# Isolation.net
KiCad netlist of a schematic drawn in Altium Designer
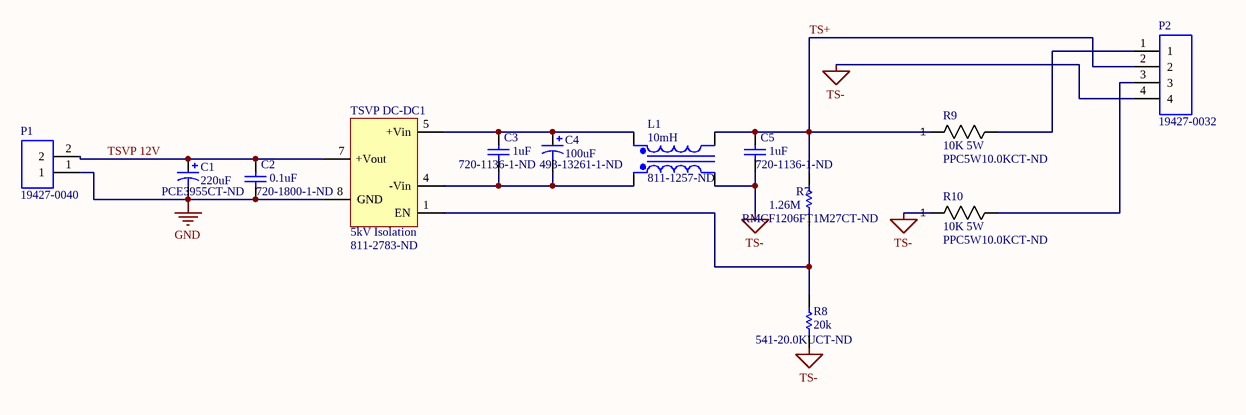
[diagram p0: Isolation.SchDoc]

(export (version "E")
  (design (tool "Eeschema 10.0.6"))
  (components
    (comp (ref "C1")
      (value "220uF")
      (footprint "EEE-1VA221UP")
      (description "Panasonic Electrolytic 35V, 20% EEE-1VA221UP")
      (fields (field (name "SUPPLIER PART NUMBER 1") "PCE3955CT-ND"))
      (libsource (lib "Isolation") (part "Cap Pol1"))
    )
    (comp (ref "C2")
      (value "0.1uF")
      (footprint "C1206")
      (description "C0603C104K3RACTU")
      (fields
        (field (name "SUPPLIER PART NUMBER 1") "720-1800-1-ND")
        (field (name "Comment") "C0603")
        (field (name "PUBLISHER") "Altium Limited")
      )
      (libsource (lib "Isolation") (part "C0603"))
    )
    (comp (ref "C3")
      (value "1uF")
      (footprint "2225 Package")
      (description "C0603C104K3RACTU")
      (fields
        (field (name "SUPPLIER PART NUMBER 1") "720-1136-1-ND")
        (field (name "Comment") "C0603")
        (field (name "PUBLISHER") "Altium Limited")
      )
      (libsource (lib "Isolation") (part "C0603_1"))
    )
    (comp (ref "C4")
      (value "100uF")
      (footprint "NichiconCAP")
      (description "Nichicon 200V 100uF TH Capacitor  UCA2D101MHD6TN")
      (fields (field (name "SUPPLIER PART NUMBER 1") "493-13261-1-ND"))
      (libsource (lib "Isolation") (part "Cap Pol1_1"))
    )
    (comp (ref "C5")
      (value "1uF")
      (footprint "2225 Package")
      (description "C0603C104K3RACTU")
      (fields
        (field (name "SUPPLIER PART NUMBER 1") "720-1136-1-ND")
        (field (name "Comment") "C0603")
        (field (name "PUBLISHER") "Altium Limited")
      )
      (libsource (lib "Isolation") (part "C0603_1"))
    )
    (comp (ref "L1")
      (value "10mH")
      (footprint "52106C")
      (description "MuRata 52106C Common Choke")
      (fields
        (field (name "SUPPLIER PART NUMBER 1") "811-1257-ND")
        (field (name "PUBLISHER") "Altium Limited")
      )
      (libsource (lib "Isolation") (part "Trans Ideal"))
    )
    (comp (ref "P1")
      (value "19427-0040")
      (footprint "MX150L 2pin")
      (description "MX150L 2pin")
      (libsource (lib "Integrated_Library1") (part "19427-0040 MX150L 2pin"))
    )
    (comp (ref "P2")
      (value "19427-0032")
      (footprint "MX150L 4pin")
      (description "MX150L 4pin")
      (libsource (lib "Integrated_Library1") (part "19427-0032 MX150L 4pin_1"))
    )
    (comp (ref "R7")
      (value "1.26M")
      (footprint "C1206")
      (description "Resistor")
      (fields
        (field (name "SUPPLIER PART NUMBER 1") "RMCF1206FT1M27CT-ND")
        (field (name "Comment") "Res1")
        (field (name "PUBLISHER") "Altium Limited")
      )
      (libsource (lib "Isolation") (part "Res1"))
    )
    (comp (ref "R8")
      (value "20k")
      (footprint "C1206")
      (description "Precision Thick Film Chip Resistor, 10 Ohm to 2.2M Ohm Range, 1% Tolerance, 0805 Size, 0.1 W")
      (fields
        (field (name "SUPPLIER PART NUMBER 1") "541-20.0KUCT-ND")
        (field (name "PUBLISHER") "Altium Limited")
      )
      (libsource (lib "Isolation") (part "ERJ6EN"))
    )
    (comp (ref "R9")
      (value "10K 5W")
      (footprint "Res THRU Hole 10k 5W")
      (fields (field (name "SUPPLIER PART NUMBER 1") "PPC5W10.0KCT-ND"))
      (libsource (lib "Isolation") (part "Resistor 10kOhm 5W"))
    )
    (comp (ref "R10")
      (value "10K 5W")
      (footprint "Res THRU Hole 10k 5W")
      (fields (field (name "SUPPLIER PART NUMBER 1") "PPC5W10.0KCT-ND"))
      (libsource (lib "Isolation") (part "Resistor 10kOhm 5W"))
    )
    (comp (ref "TSVP DC-DC1")
      (value "RUW15SL 12C")
      (footprint "RUW15SL 12C")
      (fields (field (name "NOTE") "5kV Isolation") (field (name "SUPPLIER PART NUMBER 1") "811-2783-ND"))
      (libsource (lib "Isolation") (part "RUW15SL 12C"))
    )
  )
  (nets
    (net (code "1") (name "/TS+") (class "Default")
      (node (ref "C5") (pin "2") (pinfunction "2_2") (pintype "passive"))
      (node (ref "L1") (pin "3") (pintype "passive"))
      (node (ref "P2") (pin "2") (pinfunction "2_2") (pintype "passive"))
      (node (ref "R7") (pin "2") (pinfunction "2_2") (pintype "passive"))
      (node (ref "R9") (pin "1") (pinfunction "1_1") (pintype "passive"))
    )
    (net (code "2") (name "/TSVP 12V") (class "Default")
      (node (ref "C1") (pin "1") (pinfunction "1_1") (pintype "passive"))
      (node (ref "C2") (pin "2") (pinfunction "2_2") (pintype "passive"))
      (node (ref "P1") (pin "2") (pinfunction "2_2") (pintype "passive"))
      (node (ref "TSVP DC-DC1") (pin "7") (pinfunction "+Vout_7") (pintype "passive"))
    )
    (net (code "3") (name "GND") (class "Default")
      (node (ref "C1") (pin "2") (pinfunction "2_2") (pintype "passive"))
      (node (ref "C2") (pin "1") (pinfunction "1_1") (pintype "passive"))
      (node (ref "P1") (pin "1") (pinfunction "1_1") (pintype "passive"))
      (node (ref "TSVP DC-DC1") (pin "8") (pinfunction "GND_8") (pintype "passive"))
    )
    (net (code "4") (name "Net-(P2-Pad1)") (class "Default")
      (node (ref "P2") (pin "1") (pinfunction "1_1") (pintype "passive"))
      (node (ref "R9") (pin "2") (pinfunction "2_2") (pintype "passive"))
    )
    (net (code "5") (name "Net-(P2-Pad3)") (class "Default")
      (node (ref "P2") (pin "3") (pinfunction "3_3") (pintype "passive"))
      (node (ref "R10") (pin "2") (pinfunction "2_2") (pintype "passive"))
    )
    (net (code "6") (name "Net-(TSVP DC-DC1-+Vin)") (class "Default")
      (node (ref "C3") (pin "2") (pinfunction "2_2") (pintype "passive"))
      (node (ref "C4") (pin "1") (pinfunction "1_1") (pintype "passive"))
      (node (ref "L1") (pin "2") (pintype "passive"))
      (node (ref "TSVP DC-DC1") (pin "5") (pinfunction "+Vin_5") (pintype "passive"))
    )
    (net (code "7") (name "Net-(TSVP DC-DC1--Vin)") (class "Default")
      (node (ref "C3") (pin "1") (pinfunction "1_1") (pintype "passive"))
      (node (ref "C4") (pin "2") (pinfunction "2_2") (pintype "passive"))
      (node (ref "L1") (pin "1") (pintype "passive"))
      (node (ref "TSVP DC-DC1") (pin "4") (pinfunction "-Vin_4") (pintype "passive"))
    )
    (net (code "8") (name "Net-(TSVP DC-DC1-EN)") (class "Default")
      (node (ref "R7") (pin "1") (pinfunction "1_1") (pintype "passive"))
      (node (ref "R8") (pin "2") (pinfunction "2_2") (pintype "passive"))
      (node (ref "TSVP DC-DC1") (pin "1") (pinfunction "EN_1") (pintype "passive"))
    )
    (net (code "9") (name "TS-") (class "Default")
      (node (ref "C5") (pin "1") (pinfunction "1_1") (pintype "passive"))
      (node (ref "L1") (pin "4") (pintype "passive"))
      (node (ref "P2") (pin "4") (pinfunction "4_4") (pintype "passive"))
      (node (ref "R10") (pin "1") (pinfunction "1_1") (pintype "passive"))
      (node (ref "R8") (pin "1") (pinfunction "1_1") (pintype "passive"))
    )
  )
)
